# encoder-switch-type2-tht.net
KiCad netlist of a schematic drawn in EAGLE
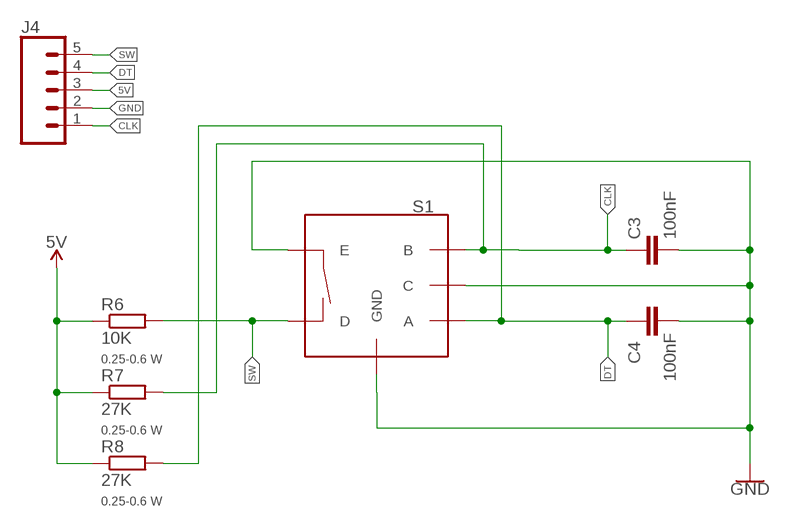
[diagram p0: schematic, sheet 1]

(export (version "E")
  (design (tool "Eeschema 10.0.6"))
  (components
    (comp (ref "C3")
      (value "100nF")
      (footprint "eagle-import:C025-024X044")
      (libsource (lib "eagle-import") (part "CAPACITOR_1025-024X044"))
    )
    (comp (ref "C4")
      (value "100nF")
      (footprint "eagle-import:C025-024X044")
      (libsource (lib "eagle-import") (part "CAPACITOR_1025-024X044"))
    )
    (comp (ref "J4")
      (value "CONN_051X05LA")
      (footprint "eagle-import:1X05_90")
      (libsource (lib "eagle-import") (part "CONN_051X05LA"))
    )
    (comp (ref "R6")
      (value "10K")
      (footprint "eagle-import:0204V")
      (fields (field (name "POWER") "0.25-0.6 W"))
      (libsource (lib "eagle-import") (part "RESISTOR0204/2V"))
    )
    (comp (ref "R7")
      (value "27K")
      (footprint "eagle-import:0204V")
      (fields (field (name "POWER") "0.25-0.6 W"))
      (libsource (lib "eagle-import") (part "RESISTOR0204/2V"))
    )
    (comp (ref "R8")
      (value "27K")
      (footprint "eagle-import:0204V")
      (fields (field (name "POWER") "0.25-0.6 W"))
      (libsource (lib "eagle-import") (part "RESISTOR0204/2V"))
    )
    (comp (ref "S1")
      (value "ENCODER_SWITCH")
      (footprint "eagle-import:ROTARY_ENC_PLAIN")
      (libsource (lib "eagle-import") (part "ENCODER_SWITCH"))
    )
  )
  (nets
    (net (code "1") (name "5V") (class "Default")
      (node (ref "J4") (pin "3") (pinfunction "3_3") (pintype "passive"))
      (node (ref "R6") (pin "1") (pinfunction "1_1") (pintype "passive"))
      (node (ref "R7") (pin "1") (pinfunction "1_1") (pintype "passive"))
      (node (ref "R8") (pin "1") (pinfunction "1_1") (pintype "passive"))
    )
    (net (code "2") (name "CLK") (class "Default")
      (node (ref "C3") (pin "1") (pinfunction "1_1") (pintype "passive"))
      (node (ref "J4") (pin "1") (pinfunction "1_1") (pintype "passive"))
      (node (ref "R7") (pin "2") (pinfunction "2_2") (pintype "passive"))
      (node (ref "S1") (pin "B") (pinfunction "B_B") (pintype "bidirectional"))
    )
    (net (code "3") (name "DT") (class "Default")
      (node (ref "C4") (pin "1") (pinfunction "1_1") (pintype "passive"))
      (node (ref "J4") (pin "4") (pinfunction "4_4") (pintype "passive"))
      (node (ref "R8") (pin "2") (pinfunction "2_2") (pintype "passive"))
      (node (ref "S1") (pin "A") (pinfunction "A_A") (pintype "bidirectional"))
    )
    (net (code "4") (name "GND") (class "Default")
      (node (ref "C3") (pin "2") (pinfunction "2_2") (pintype "passive"))
      (node (ref "C4") (pin "2") (pinfunction "2_2") (pintype "passive"))
      (node (ref "J4") (pin "2") (pinfunction "2_2") (pintype "passive"))
      (node (ref "S1") (pin "C") (pinfunction "C_C") (pintype "bidirectional"))
      (node (ref "S1") (pin "E") (pinfunction "E_E") (pintype "bidirectional"))
      (node (ref "S1") (pin "GND1") (pinfunction "GND_GND1") (pintype "bidirectional"))
      (node (ref "S1") (pin "GND2") (pinfunction "GND_GND2") (pintype "bidirectional"))
    )
    (net (code "5") (name "SW") (class "Default")
      (node (ref "J4") (pin "5") (pinfunction "5_5") (pintype "passive"))
      (node (ref "R6") (pin "2") (pinfunction "2_2") (pintype "passive"))
      (node (ref "S1") (pin "D") (pinfunction "D_D") (pintype "bidirectional"))
    )
  )
)
